# MY_beamControl_R.net
KiCad netlist of a schematic drawn in Altium Designer
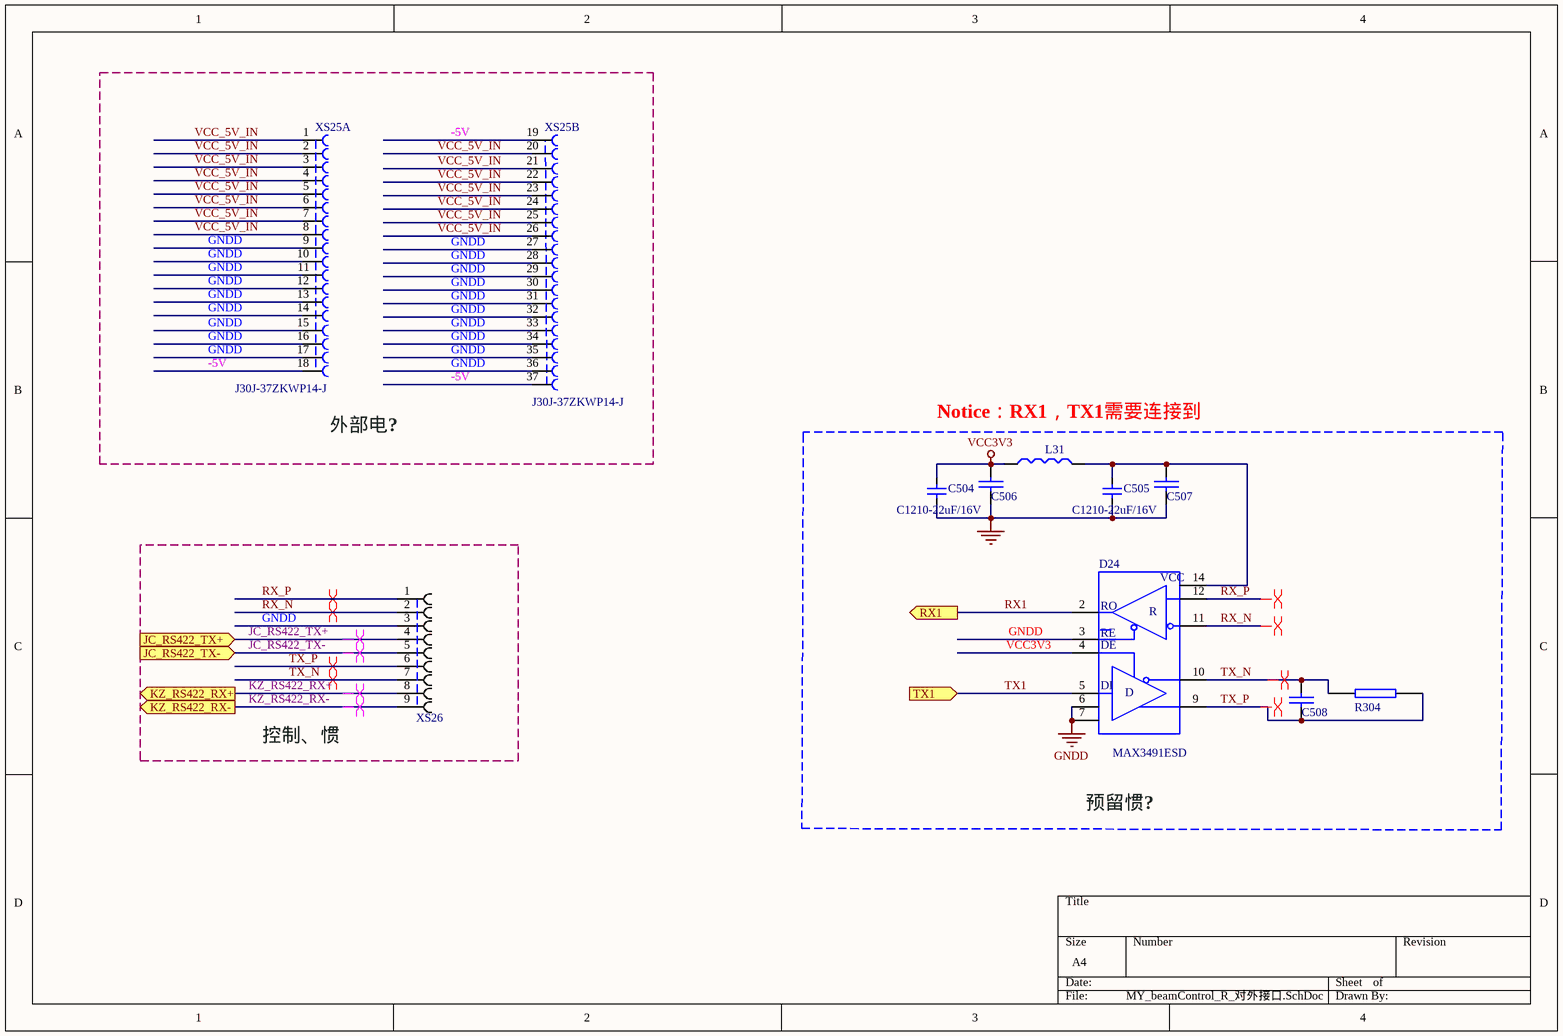
[diagram p0: MY_beamControl_R_对外接口.SchDoc]

(export (version "E")
  (design (tool "Eeschema 10.0.6"))
  (components
    (comp (ref "C504")
      (value "C1210-22uF/16V")
      (footprint "C1210")
      (fields (field (name "SCHEMATIC_PART") "CAP"))
      (libsource (lib "Database_Libs1") (part "CAP"))
    )
    (comp (ref "C505")
      (value "C1210-22uF/16V")
      (footprint "C1210")
      (fields (field (name "SCHEMATIC_PART") "CAP"))
      (libsource (lib "Database_Libs1") (part "CAP"))
    )
    (comp (ref "C506")
      (value "C0402-0.1uF/16V")
      (footprint "c0402")
      (libsource (lib "mySchLib") (part "C_2"))
    )
    (comp (ref "C507")
      (value "C0402-0.1uF/16V")
      (footprint "c0402")
      (libsource (lib "mySchLib") (part "C_2"))
    )
    (comp (ref "C508")
      (value "C0402-0.1uF/16V")
      (footprint "c0402")
      (libsource (lib "mySchLib") (part "C_2"))
    )
    (comp (ref "D24") (value "MAX3491ESD") (footprint "SO-14") (libsource (lib "*") (part "MAX1482")))
    (comp (ref "L31")
      (value "MPZ2012S101A")
      (footprint "R0805")
      (libsource (lib "*") (part "ProE2A0.TMP_UnNamed_1"))
    )
    (comp (ref "R304") (value "0603-121(120Ω)") (footprint "R0603") (libsource (lib "*") (part "RES2")))
    (comp (ref "XS25")
      (value "J30J-37ZKWP14-J")
      (footprint "J30J-37ZKWP14")
      (libsource (lib "mySchLib") (part "37PIN"))
    )
    (comp (ref "XS26")
      (value "J30J-9ZKWP7-J(成套订购)")
      (footprint "J30J-9ZKWP7-J")
      (description "9芯D型连接器")
      (libsource (lib "standard_lib") (part "DB9_2"))
    )
  )
  (nets
    (net (code "1") (name "/-5V") (class "Default")
      (node (ref "XS25") (pin "18") (pintype "passive"))
      (node (ref "XS25") (pin "19") (pintype "passive"))
      (node (ref "XS25") (pin "37") (pintype "passive"))
    )
    (net (code "2") (name "/JC_RS422_TX+") (class "Default")
      (node (ref "XS26") (pin "4") (pintype "passive"))
    )
    (net (code "3") (name "/JC_RS422_TX-") (class "Default")
      (node (ref "XS26") (pin "5") (pintype "passive"))
    )
    (net (code "4") (name "/KZ_RS422_RX+") (class "Default")
      (node (ref "XS26") (pin "8") (pintype "passive"))
    )
    (net (code "5") (name "/KZ_RS422_RX-") (class "Default")
      (node (ref "XS26") (pin "9") (pintype "passive"))
    )
    (net (code "6") (name "/RX1") (class "Default") (node (ref "D24") (pin "2") (pintype "passive")))
    (net (code "7") (name "/RX_N") (class "Default")
      (node (ref "D24") (pin "11") (pintype "passive"))
      (node (ref "XS26") (pin "2") (pintype "passive"))
    )
    (net (code "8") (name "/RX_P") (class "Default")
      (node (ref "D24") (pin "12") (pintype "passive"))
      (node (ref "XS26") (pin "1") (pintype "passive"))
    )
    (net (code "9") (name "/TX1") (class "Default") (node (ref "D24") (pin "5") (pintype "passive")))
    (net (code "10") (name "/TX_N") (class "Default")
      (node (ref "C508") (pin "1") (pintype "passive"))
      (node (ref "D24") (pin "10") (pintype "passive"))
      (node (ref "R304") (pin "2") (pinfunction "2_2") (pintype "passive"))
      (node (ref "XS26") (pin "7") (pintype "passive"))
    )
    (net (code "11") (name "/TX_P") (class "Default")
      (node (ref "C508") (pin "2") (pintype "passive"))
      (node (ref "D24") (pin "9") (pintype "passive"))
      (node (ref "R304") (pin "1") (pinfunction "1_1") (pintype "passive"))
      (node (ref "XS26") (pin "6") (pintype "passive"))
    )
    (net (code "12") (name "/VCC_5V_IN") (class "Default")
      (node (ref "XS25") (pin "1") (pintype "passive"))
      (node (ref "XS25") (pin "2") (pintype "passive"))
      (node (ref "XS25") (pin "20") (pintype "passive"))
      (node (ref "XS25") (pin "21") (pintype "passive"))
      (node (ref "XS25") (pin "22") (pintype "passive"))
      (node (ref "XS25") (pin "23") (pintype "passive"))
      (node (ref "XS25") (pin "24") (pintype "passive"))
      (node (ref "XS25") (pin "25") (pintype "passive"))
      (node (ref "XS25") (pin "26") (pintype "passive"))
      (node (ref "XS25") (pin "3") (pintype "passive"))
      (node (ref "XS25") (pin "4") (pintype "passive"))
      (node (ref "XS25") (pin "5") (pintype "passive"))
      (node (ref "XS25") (pin "6") (pintype "passive"))
      (node (ref "XS25") (pin "7") (pintype "passive"))
      (node (ref "XS25") (pin "8") (pintype "passive"))
    )
    (net (code "13") (name "GNDD") (class "Default")
      (node (ref "C504") (pin "2") (pinfunction "2_2") (pintype "passive"))
      (node (ref "C505") (pin "2") (pinfunction "2_2") (pintype "passive"))
      (node (ref "C506") (pin "2") (pintype "passive"))
      (node (ref "C507") (pin "2") (pintype "passive"))
      (node (ref "D24") (pin "3") (pintype "passive"))
      (node (ref "D24") (pin "6") (pintype "passive"))
      (node (ref "D24") (pin "7") (pinfunction "GND_7") (pintype "passive"))
      (node (ref "XS25") (pin "10") (pintype "passive"))
      (node (ref "XS25") (pin "11") (pintype "passive"))
      (node (ref "XS25") (pin "12") (pintype "passive"))
      (node (ref "XS25") (pin "13") (pintype "passive"))
      (node (ref "XS25") (pin "14") (pintype "passive"))
      (node (ref "XS25") (pin "15") (pintype "passive"))
      (node (ref "XS25") (pin "16") (pintype "passive"))
      (node (ref "XS25") (pin "17") (pintype "passive"))
      (node (ref "XS25") (pin "27") (pintype "passive"))
      (node (ref "XS25") (pin "28") (pintype "passive"))
      (node (ref "XS25") (pin "29") (pintype "passive"))
      (node (ref "XS25") (pin "30") (pintype "passive"))
      (node (ref "XS25") (pin "31") (pintype "passive"))
      (node (ref "XS25") (pin "32") (pintype "passive"))
      (node (ref "XS25") (pin "33") (pintype "passive"))
      (node (ref "XS25") (pin "34") (pintype "passive"))
      (node (ref "XS25") (pin "35") (pintype "passive"))
      (node (ref "XS25") (pin "36") (pintype "passive"))
      (node (ref "XS25") (pin "9") (pintype "passive"))
      (node (ref "XS26") (pin "3") (pintype "passive"))
    )
    (net (code "14") (name "Net-(D24-VCC)") (class "Default")
      (node (ref "C505") (pin "1") (pinfunction "1_1") (pintype "passive"))
      (node (ref "C507") (pin "1") (pintype "passive"))
      (node (ref "D24") (pin "14") (pinfunction "VCC_14") (pintype "power_in"))
      (node (ref "L31") (pin "2") (pintype "passive"))
    )
    (net (code "15") (name "VCC3V3") (class "Default")
      (node (ref "C504") (pin "1") (pinfunction "1_1") (pintype "passive"))
      (node (ref "C506") (pin "1") (pintype "passive"))
      (node (ref "D24") (pin "4") (pintype "passive"))
      (node (ref "L31") (pin "1") (pintype "passive"))
    )
  )
)
